# Connectors_CSA.net
KiCad netlist of a schematic drawn in Altium Designer
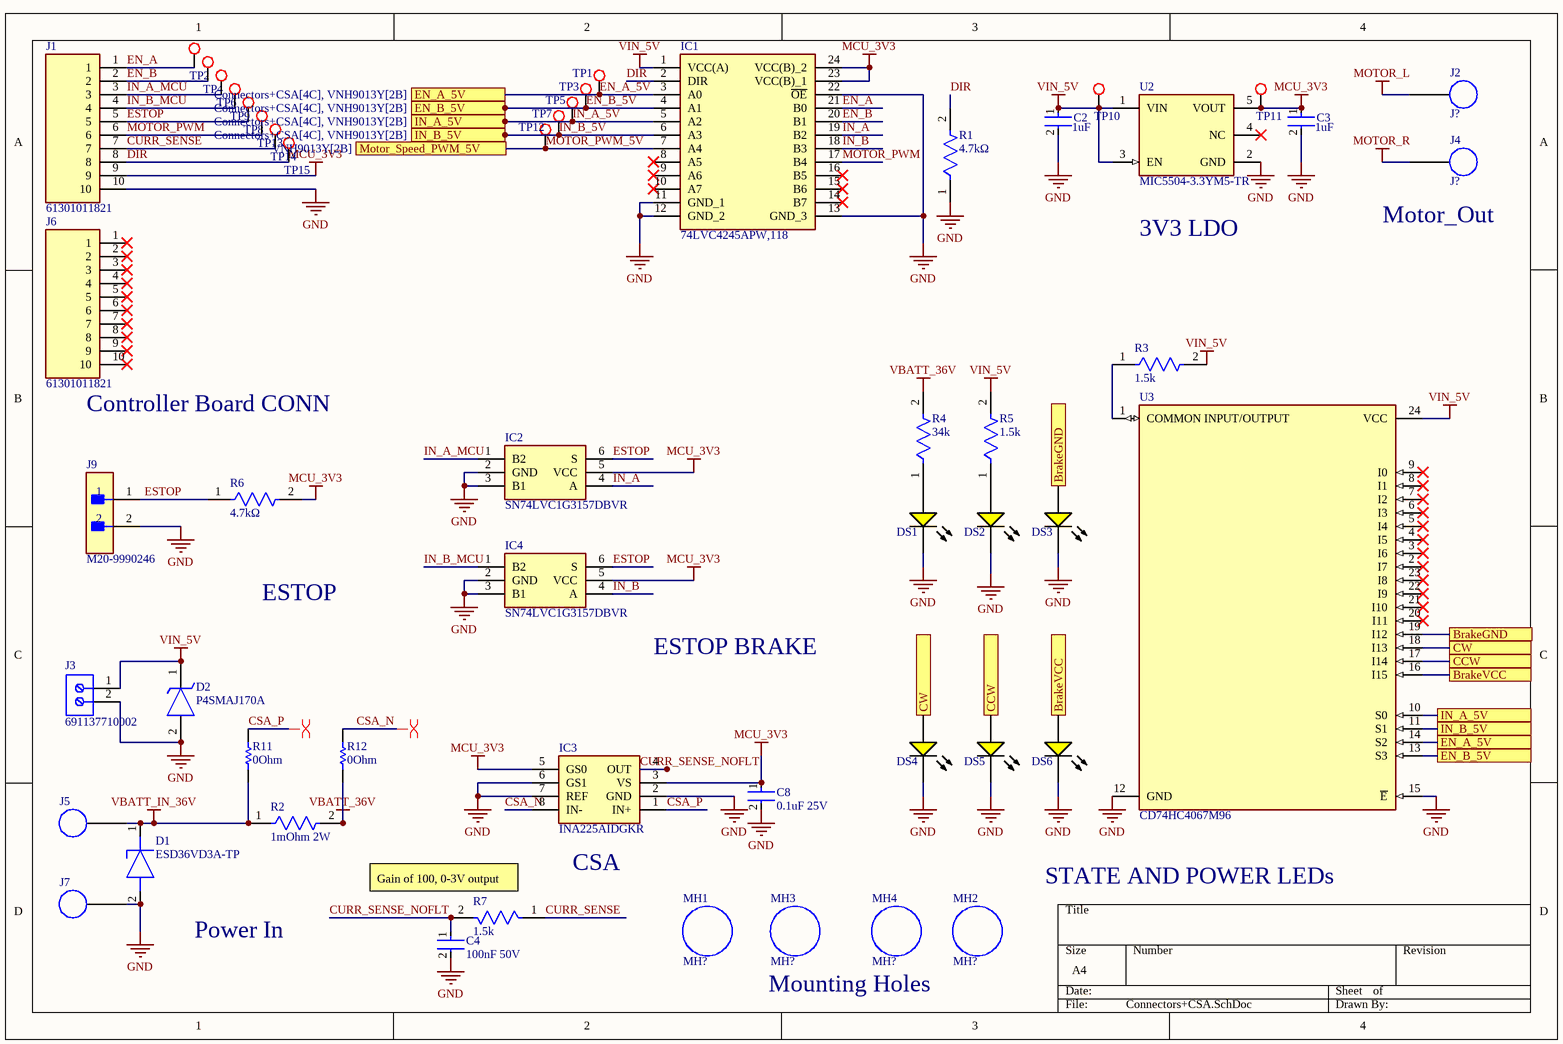
[diagram p0: Connectors+CSA.SchDoc]

(export (version "E")
  (design (tool "Eeschema 10.0.6"))
  (components
    (comp (ref "C2")
      (value "1uF")
      (footprint "FP-CL10-IPC_C")
      (description "Cap Ceramic 1uF 10V X5R ±10% Pad SMD 0603 +85°C T/R")
      (fields (field (name "VOLTAGE") "10V") (field (name "TOLERANCE") "10%"))
      (libsource (lib "Altium Content Vault") (part "b4654b650e69147ec39a6b967a45e02"))
    )
    (comp (ref "C3")
      (value "1uF")
      (footprint "FP-CL10-IPC_C")
      (description "Cap Ceramic 1uF 10V X5R ±10% Pad SMD 0603 +85°C T/R")
      (fields (field (name "VOLTAGE") "10V") (field (name "TOLERANCE") "10%"))
      (libsource (lib "Altium Content Vault") (part "b4654b650e69147ec39a6b967a45e02"))
    )
    (comp (ref "C4")
      (value "100nF 50V")
      (footprint "FP-CL31-IPC_C")
      (description "Cap Ceramic 100nF 50V X7R ±10% SMD 1206 +125°C Embossed T/R")
      (fields (field (name "TOLERANCE") "10%"))
      (libsource (lib "Altium Content Vault") (part "b4654b650e69147ec39a6b967a45e02"))
    )
    (comp (ref "C8")
      (value "0.1uF 25V")
      (footprint "FP-CL21-IPC_C")
      (description "CL21 Series 0805 100nF 25V -20/+80% Tolerance Y5V Multilayer Ceramic Chip Capacitor")
      (fields (field (name "TOLERANCE") "80%"))
      (libsource (lib "Altium Content Vault") (part "b4654b650e69147ec39a6b967a45e02"))
    )
    (comp (ref "D1")
      (value "ESD36VD3A-TP")
      (footprint "SamacSys:SOD2512X115N")
      (description "Diode ESD (Uni-directional)")
      (libsource (lib "*") (part "ESD36VD3A-TP"))
    )
    (comp (ref "D2")
      (value "P4SMAJ170A")
      (footprint "SamacSys:DIOM5027X240N")
      (description "TVS Diode (Uni-directional)")
      (libsource (lib "*") (part "P4SMAJ170A"))
    )
    (comp (ref "DS1")
      (value "HSMY-C190")
      (footprint "AVAG-HSMX-C190_V")
      (description "LED Uni-Color Yellow, 65 mW, 20 mA, -40 to 85 degC, 2-Pin SMD, RoHS, Tape and Reel")
      (fields (field (name "TOLERANCE") "1%"))
      (libsource (lib "Altium Content Vault") (part "LED-YELLOW-AK-2"))
    )
    (comp (ref "DS2")
      (value "HSMY-C190")
      (footprint "AVAG-HSMX-C190_V")
      (description "LED Uni-Color Yellow, 65 mW, 20 mA, -40 to 85 degC, 2-Pin SMD, RoHS, Tape and Reel")
      (fields (field (name "TOLERANCE") "1%"))
      (libsource (lib "Altium Content Vault") (part "LED-YELLOW-AK-2"))
    )
    (comp (ref "DS3")
      (value "HSMY-C190")
      (footprint "AVAG-HSMX-C190_V")
      (description "LED Uni-Color Yellow, 65 mW, 20 mA, -40 to 85 degC, 2-Pin SMD, RoHS, Tape and Reel")
      (fields (field (name "TOLERANCE") "1%"))
      (libsource (lib "Altium Content Vault") (part "LED-YELLOW-AK-2"))
    )
    (comp (ref "DS4")
      (value "HSMY-C190")
      (footprint "AVAG-HSMX-C190_V")
      (description "LED Uni-Color Yellow, 65 mW, 20 mA, -40 to 85 degC, 2-Pin SMD, RoHS, Tape and Reel")
      (fields (field (name "TOLERANCE") "1%"))
      (libsource (lib "Altium Content Vault") (part "LED-YELLOW-AK-2"))
    )
    (comp (ref "DS5")
      (value "HSMY-C190")
      (footprint "AVAG-HSMX-C190_V")
      (description "LED Uni-Color Yellow, 65 mW, 20 mA, -40 to 85 degC, 2-Pin SMD, RoHS, Tape and Reel")
      (fields (field (name "TOLERANCE") "1%"))
      (libsource (lib "Altium Content Vault") (part "LED-YELLOW-AK-2"))
    )
    (comp (ref "DS6")
      (value "HSMY-C190")
      (footprint "AVAG-HSMX-C190_V")
      (description "LED Uni-Color Yellow, 65 mW, 20 mA, -40 to 85 degC, 2-Pin SMD, RoHS, Tape and Reel")
      (fields (field (name "TOLERANCE") "1%"))
      (libsource (lib "Altium Content Vault") (part "LED-YELLOW-AK-2"))
    )
    (comp (ref "IC1")
      (value "74LVC4245APW,118")
      (footprint "SamacSys:SOP65P640X110-24N")
      (description "Integrated Circuit")
      (fields (field (name "MOUSER PART NUMBER") "771-74LVC4245APW-T"))
      (libsource (lib "*") (part "74LVC4245APW,118"))
    )
    (comp (ref "IC2")
      (value "SN74LVC1G3157DBVR")
      (footprint "SamacSys:SOT95P280X145-6N")
      (description "Integrated Circuit")
      (fields (field (name "MOUSER PART NUMBER") "595-SN74LVC1G3157DBV"))
      (libsource (lib "*") (part "SN74LVC1G3157DBVR"))
    )
    (comp (ref "IC3")
      (value "INA225AIDGKR")
      (footprint "SamacSys:SOP65P490X110-8N")
      (description "Integrated Circuit")
      (libsource (lib "*") (part "INA225AIDGKR"))
    )
    (comp (ref "IC4")
      (value "SN74LVC1G3157DBVR")
      (footprint "SamacSys:SOT95P280X145-6N")
      (description "Integrated Circuit")
      (fields (field (name "MOUSER PART NUMBER") "595-SN74LVC1G3157DBV"))
      (libsource (lib "*") (part "SN74LVC1G3157DBVR"))
    )
    (comp (ref "J1")
      (value "61301011821")
      (footprint "SamacSys:RHDR10W60P0X254_1X10_2590X250X850P")
      (description "Connector")
      (fields (field (name "MOUSER PART NUMBER") "710-61301011821"))
      (libsource (lib "*") (part "61301011821"))
    )
    (comp (ref "J2")
      (value "J?")
      (footprint "Power Screw Terminal")
      (libsource (lib "Schlib1") (part "Screw Connector"))
    )
    (comp (ref "J3")
      (value "691137710002")
      (footprint "691137710002")
      (libsource (lib "Altium Content Vault") (part "TBL - 1R - 02P - Screw"))
    )
    (comp (ref "J4")
      (value "J?")
      (footprint "Power Screw Terminal")
      (libsource (lib "Schlib1") (part "Screw Connector"))
    )
    (comp (ref "J5")
      (value "J?")
      (footprint "Power Screw Terminal")
      (libsource (lib "Schlib1") (part "Screw Connector"))
    )
    (comp (ref "J6")
      (value "61301011821")
      (footprint "SamacSys:RHDR10W60P0X254_1X10_2590X250X850P")
      (description "Connector")
      (fields (field (name "MOUSER PART NUMBER") "710-61301011821"))
      (libsource (lib "*") (part "61301011821"))
    )
    (comp (ref "J7")
      (value "J?")
      (footprint "Power Screw Terminal")
      (libsource (lib "Schlib1") (part "Screw Connector"))
    )
    (comp (ref "J9")
      (value "M20-9990246")
      (footprint "FP-M20-9990246-MFG")
      (description "CONN HEADER VERT 2POS 2.54MM")
      (fields
        (field (name "OCTOPART") "https://octopart.com/m20-9990246-harwin-2590635")
        (field (name "MANUFACTURER") "Harwin")
      )
      (libsource (lib "Altium Content Vault") (part "3bc925449376181038e59eaffc5286c"))
    )
    (comp (ref "MH1")
      (value "MH?")
      (footprint "Mounting Hole")
      (libsource (lib "Schlib1") (part "Mounting Hole"))
    )
    (comp (ref "MH2")
      (value "MH?")
      (footprint "Mounting Hole")
      (libsource (lib "Schlib1") (part "Mounting Hole"))
    )
    (comp (ref "MH3")
      (value "MH?")
      (footprint "Mounting Hole")
      (libsource (lib "Schlib1") (part "Mounting Hole"))
    )
    (comp (ref "MH4")
      (value "MH?")
      (footprint "Mounting Hole")
      (libsource (lib "Schlib1") (part "Mounting Hole"))
    )
    (comp (ref "R1")
      (value "4.7kΩ")
      (footprint "FP-RT0805-MFG")
      (description "RES SMD 4.7K OHM 1% 1/8W 0805")
      (fields (field (name "TOLERANCE") "0.0001") (field (name "MANUFACTURER PART NUMBER") "RT0805FRE074K7L"))
      (libsource (lib "Altium Content Vault") (part "1029c3af85768c4190bb7ad29bc67b5"))
    )
    (comp (ref "R2")
      (value "1mOhm 2W")
      (footprint "FP-WSL2512-MFG")
      (fields (field (name "TOLERANCE") "1%"))
      (libsource (lib "Altium Content Vault") (part "1029c3af85768c4190bb7ad29bc67b5"))
    )
    (comp (ref "R3")
      (value "1.5k")
      (footprint "FP-RC1608-IPC_B")
      (description "Res Thick Film 0603 1.5kΩ 1% 0.1W ±100ppm/°C Molded SMD T/R")
      (fields (field (name "TOLERANCE") "1%"))
      (libsource (lib "Altium Content Vault") (part "1029c3af85768c4190bb7ad29bc67b5"))
    )
    (comp (ref "R4")
      (value "34k")
      (footprint "FP-CRCW0805-e3-IPC_B")
      (description "RES Thick Film, 34kΩ, 1%, 0.125W, 100ppm/°C, 0805")
      (fields (field (name "TOLERANCE") "1%"))
      (libsource (lib "Altium Content Vault") (part "1029c3af85768c4190bb7ad29bc67b5"))
    )
    (comp (ref "R5")
      (value "1.5k")
      (footprint "FP-RC1608-IPC_B")
      (description "Res Thick Film 0603 1.5kΩ 1% 0.1W ±100ppm/°C Molded SMD T/R")
      (fields (field (name "TOLERANCE") "1%"))
      (libsource (lib "Altium Content Vault") (part "1029c3af85768c4190bb7ad29bc67b5"))
    )
    (comp (ref "R6")
      (value "4.7kΩ")
      (footprint "FP-RT0805-MFG")
      (description "RES SMD 4.7K OHM 1% 1/8W 0805")
      (fields (field (name "TOLERANCE") "0.0001") (field (name "MANUFACTURER PART NUMBER") "RT0805FRE074K7L"))
      (libsource (lib "Altium Content Vault") (part "1029c3af85768c4190bb7ad29bc67b5"))
    )
    (comp (ref "R7")
      (value "1.5k")
      (footprint "FP-CRCW0603-e3-IPC_A")
      (description "RES Thick Film, 1.5kΩ, 1%, 0.1W, 100ppm/°C, 0603")
      (fields (field (name "TOLERANCE") "1%"))
      (libsource (lib "Altium Content Vault") (part "1029c3af85768c4190bb7ad29bc67b5"))
    )
    (comp (ref "R11")
      (value "0Ohm")
      (footprint "RESC2013X60X35LL10T20")
      (description "Chip Resistor, 0 Ohm, +/- 5%, 125 mW, -55 to 155 degC, 0805 (2012 Metric), RoHS, Tape and Reel")
      (fields (field (name "MANUFACTURER") "Yageo"))
      (libsource (lib "Altium Content Vault") (part "RES-2"))
    )
    (comp (ref "R12")
      (value "0Ohm")
      (footprint "RESC2013X60X35LL10T20")
      (description "Chip Resistor, 0 Ohm, +/- 5%, 125 mW, -55 to 155 degC, 0805 (2012 Metric), RoHS, Tape and Reel")
      (fields (field (name "MANUFACTURER") "Yageo"))
      (libsource (lib "Altium Content Vault") (part "RES-2"))
    )
    (comp (ref "TP1") (value "TP") (footprint "Testpoint") (libsource (lib "Schlib1") (part "Testpoint")))
    (comp (ref "TP2") (value "TP") (footprint "Testpoint") (libsource (lib "Schlib1") (part "Testpoint")))
    (comp (ref "TP3") (value "TP") (footprint "Testpoint") (libsource (lib "Schlib1") (part "Testpoint")))
    (comp (ref "TP4") (value "TP") (footprint "Testpoint") (libsource (lib "Schlib1") (part "Testpoint")))
    (comp (ref "TP5") (value "TP") (footprint "Testpoint") (libsource (lib "Schlib1") (part "Testpoint")))
    (comp (ref "TP6") (value "TP") (footprint "Testpoint") (libsource (lib "Schlib1") (part "Testpoint")))
    (comp (ref "TP7") (value "TP") (footprint "Testpoint") (libsource (lib "Schlib1") (part "Testpoint")))
    (comp (ref "TP8") (value "TP") (footprint "Testpoint") (libsource (lib "Schlib1") (part "Testpoint")))
    (comp (ref "TP9") (value "TP") (footprint "Testpoint") (libsource (lib "Schlib1") (part "Testpoint")))
    (comp (ref "TP10") (value "TP") (footprint "Testpoint") (libsource (lib "Schlib1") (part "Testpoint")))
    (comp (ref "TP11") (value "TP") (footprint "Testpoint") (libsource (lib "Schlib1") (part "Testpoint")))
    (comp (ref "TP12") (value "TP") (footprint "Testpoint") (libsource (lib "Schlib1") (part "Testpoint")))
    (comp (ref "TP13") (value "TP") (footprint "Testpoint") (libsource (lib "Schlib1") (part "Testpoint")))
    (comp (ref "TP14") (value "TP") (footprint "Testpoint") (libsource (lib "Schlib1") (part "Testpoint")))
    (comp (ref "TP15") (value "TP") (footprint "Testpoint") (libsource (lib "Schlib1") (part "Testpoint")))
    (comp (ref "U2")
      (value "MIC5504-3.3YM5-TR")
      (footprint "FP-SOT23-5LD-PL-1-MFG")
      (description "IC REG LINEAR 3.3V 300MA SOT23-5")
      (libsource (lib "Altium Content Vault") (part "96048095611b4a9579e1e315950d302"))
    )
    (comp (ref "U3")
      (value "CD74HC4067M96")
      (footprint "FP-DW0024A-MFG")
      (description "IC MUX/DEMUX 1X16 24SOIC")
      (fields
        (field (name "OCTOPART") "https://octopart.com/cd74hc4067m96-texas+instruments-722802")
        (field (name "MANUFACTURER") "Texas Instruments")
      )
      (libsource (lib "Altium Content Vault") (part "0e3014a41e7f600214dac1b4fa06845"))
    )
  )
  (nets
    (net (code "1") (name "/BrakeGND") (class "Default")
      (node (ref "DS3") (pin "1") (pinfunction "A_1") (pintype "passive"))
      (node (ref "U3") (pin "19") (pinfunction "I12_19") (pintype "input"))
    )
    (net (code "2") (name "/BrakeVCC") (class "Default")
      (node (ref "DS6") (pin "1") (pinfunction "A_1") (pintype "passive"))
      (node (ref "U3") (pin "16") (pinfunction "I15_16") (pintype "input"))
    )
    (net (code "3") (name "/CCW") (class "Default")
      (node (ref "DS5") (pin "1") (pinfunction "A_1") (pintype "passive"))
      (node (ref "U3") (pin "17") (pinfunction "I14_17") (pintype "input"))
    )
    (net (code "4") (name "/CSA_N") (class "Default")
      (node (ref "IC3") (pin "8") (pinfunction "IN-_8") (pintype "passive"))
      (node (ref "R12") (pin "1") (pinfunction "1_1") (pintype "passive"))
    )
    (net (code "5") (name "/CSA_P") (class "Default")
      (node (ref "IC3") (pin "1") (pinfunction "IN+_1") (pintype "passive"))
      (node (ref "R11") (pin "1") (pinfunction "1_1") (pintype "passive"))
    )
    (net (code "6") (name "/CURR_SENSE") (class "Default")
      (node (ref "J1") (pin "7") (pinfunction "7_7") (pintype "passive"))
      (node (ref "R7") (pin "1") (pinfunction "1_1") (pintype "passive"))
      (node (ref "TP14") (pin "0") (pinfunction "0_0") (pintype "passive"))
    )
    (net (code "7") (name "/CURR_SENSE_NOFLT") (class "Default")
      (node (ref "C4") (pin "1") (pinfunction "1_1") (pintype "passive"))
      (node (ref "IC3") (pin "4") (pinfunction "OUT_4") (pintype "passive"))
      (node (ref "R7") (pin "2") (pinfunction "2_2") (pintype "passive"))
    )
    (net (code "8") (name "/CW") (class "Default")
      (node (ref "DS4") (pin "1") (pinfunction "A_1") (pintype "passive"))
      (node (ref "U3") (pin "18") (pinfunction "I13_18") (pintype "input"))
    )
    (net (code "9") (name "/DIR") (class "Default")
      (node (ref "IC1") (pin "2") (pinfunction "DIR_2") (pintype "passive"))
      (node (ref "J1") (pin "8") (pinfunction "8_8") (pintype "passive"))
      (node (ref "R1") (pin "2") (pinfunction "2_2") (pintype "passive"))
      (node (ref "TP15") (pin "0") (pinfunction "0_0") (pintype "passive"))
    )
    (net (code "10") (name "/EN_A") (class "Default")
      (node (ref "IC1") (pin "21") (pinfunction "B0_21") (pintype "passive"))
      (node (ref "J1") (pin "1") (pinfunction "1_1") (pintype "passive"))
      (node (ref "TP2") (pin "0") (pinfunction "0_0") (pintype "passive"))
    )
    (net (code "11") (name "/EN_A_5V") (class "Default")
      (node (ref "IC1") (pin "3") (pinfunction "A0_3") (pintype "passive"))
      (node (ref "TP1") (pin "0") (pinfunction "0_0") (pintype "passive"))
      (node (ref "U3") (pin "14") (pinfunction "S2_14") (pintype "input"))
    )
    (net (code "12") (name "/EN_B") (class "Default")
      (node (ref "IC1") (pin "20") (pinfunction "B1_20") (pintype "passive"))
      (node (ref "J1") (pin "2") (pinfunction "2_2") (pintype "passive"))
      (node (ref "TP4") (pin "0") (pinfunction "0_0") (pintype "passive"))
    )
    (net (code "13") (name "/EN_B_5V") (class "Default")
      (node (ref "IC1") (pin "4") (pinfunction "A1_4") (pintype "passive"))
      (node (ref "TP3") (pin "0") (pinfunction "0_0") (pintype "passive"))
      (node (ref "U3") (pin "13") (pinfunction "S3_13") (pintype "input"))
    )
    (net (code "14") (name "/ESTOP") (class "Default")
      (node (ref "IC2") (pin "6") (pinfunction "S_6") (pintype "passive"))
      (node (ref "IC4") (pin "6") (pinfunction "S_6") (pintype "passive"))
      (node (ref "J1") (pin "5") (pinfunction "5_5") (pintype "passive"))
      (node (ref "J9") (pin "1") (pinfunction "1_1") (pintype "passive"))
      (node (ref "R6") (pin "1") (pinfunction "1_1") (pintype "passive"))
      (node (ref "TP8") (pin "0") (pinfunction "0_0") (pintype "passive"))
    )
    (net (code "15") (name "/IN_A") (class "Default")
      (node (ref "IC1") (pin "19") (pinfunction "B2_19") (pintype "passive"))
      (node (ref "IC2") (pin "4") (pinfunction "A_4") (pintype "passive"))
    )
    (net (code "16") (name "/IN_A_5V") (class "Default")
      (node (ref "IC1") (pin "5") (pinfunction "A2_5") (pintype "passive"))
      (node (ref "TP5") (pin "0") (pinfunction "0_0") (pintype "passive"))
      (node (ref "U3") (pin "10") (pinfunction "S0_10") (pintype "input"))
    )
    (net (code "17") (name "/IN_A_MCU") (class "Default")
      (node (ref "IC2") (pin "1") (pinfunction "B2_1") (pintype "passive"))
      (node (ref "J1") (pin "3") (pinfunction "3_3") (pintype "passive"))
      (node (ref "TP6") (pin "0") (pinfunction "0_0") (pintype "passive"))
    )
    (net (code "18") (name "/IN_B") (class "Default")
      (node (ref "IC1") (pin "18") (pinfunction "B3_18") (pintype "passive"))
      (node (ref "IC4") (pin "4") (pinfunction "A_4") (pintype "passive"))
    )
    (net (code "19") (name "/IN_B_5V") (class "Default")
      (node (ref "IC1") (pin "6") (pinfunction "A3_6") (pintype "passive"))
      (node (ref "TP7") (pin "0") (pinfunction "0_0") (pintype "passive"))
      (node (ref "U3") (pin "11") (pinfunction "S1_11") (pintype "input"))
    )
    (net (code "20") (name "/IN_B_MCU") (class "Default")
      (node (ref "IC4") (pin "1") (pinfunction "B2_1") (pintype "passive"))
      (node (ref "J1") (pin "4") (pinfunction "4_4") (pintype "passive"))
      (node (ref "TP9") (pin "0") (pinfunction "0_0") (pintype "passive"))
    )
    (net (code "21") (name "/MOTOR_PWM") (class "Default")
      (node (ref "IC1") (pin "17") (pinfunction "B4_17") (pintype "passive"))
      (node (ref "J1") (pin "6") (pinfunction "6_6") (pintype "passive"))
      (node (ref "TP13") (pin "0") (pinfunction "0_0") (pintype "passive"))
    )
    (net (code "22") (name "/MOTOR_PWM_5V") (class "Default")
      (node (ref "IC1") (pin "7") (pinfunction "A4_7") (pintype "passive"))
      (node (ref "TP12") (pin "0") (pinfunction "0_0") (pintype "passive"))
    )
    (net (code "23") (name "GND") (class "Default")
      (node (ref "C2") (pin "2") (pinfunction "2_2") (pintype "passive"))
      (node (ref "C3") (pin "2") (pinfunction "2_2") (pintype "passive"))
      (node (ref "C4") (pin "2") (pinfunction "2_2") (pintype "passive"))
      (node (ref "C8") (pin "2") (pinfunction "2_2") (pintype "passive"))
      (node (ref "D1") (pin "2") (pinfunction "A_2") (pintype "passive"))
      (node (ref "D2") (pin "2") (pinfunction "A_2") (pintype "passive"))
      (node (ref "DS1") (pin "2") (pinfunction "K_2") (pintype "passive"))
      (node (ref "DS2") (pin "2") (pinfunction "K_2") (pintype "passive"))
      (node (ref "DS3") (pin "2") (pinfunction "K_2") (pintype "passive"))
      (node (ref "DS4") (pin "2") (pinfunction "K_2") (pintype "passive"))
      (node (ref "DS5") (pin "2") (pinfunction "K_2") (pintype "passive"))
      (node (ref "DS6") (pin "2") (pinfunction "K_2") (pintype "passive"))
      (node (ref "IC1") (pin "11") (pinfunction "GND_1_11") (pintype "passive"))
      (node (ref "IC1") (pin "12") (pinfunction "GND_2_12") (pintype "passive"))
      (node (ref "IC1") (pin "13") (pinfunction "GND_3_13") (pintype "passive"))
      (node (ref "IC1") (pin "22") (pinfunction "~{OE}_22") (pintype "passive"))
      (node (ref "IC2") (pin "2") (pinfunction "GND_2") (pintype "passive"))
      (node (ref "IC2") (pin "3") (pinfunction "B1_3") (pintype "passive"))
      (node (ref "IC3") (pin "2") (pinfunction "GND_2") (pintype "passive"))
      (node (ref "IC3") (pin "6") (pinfunction "GS1_6") (pintype "passive"))
      (node (ref "IC3") (pin "7") (pinfunction "REF_7") (pintype "passive"))
      (node (ref "IC4") (pin "2") (pinfunction "GND_2") (pintype "passive"))
      (node (ref "IC4") (pin "3") (pinfunction "B1_3") (pintype "passive"))
      (node (ref "J1") (pin "10") (pinfunction "10_10") (pintype "passive"))
      (node (ref "J3") (pin "2") (pinfunction "2_2") (pintype "passive"))
      (node (ref "J7") (pin "1") (pinfunction "1_1") (pintype "passive"))
      (node (ref "J9") (pin "2") (pinfunction "2_2") (pintype "passive"))
      (node (ref "R1") (pin "1") (pinfunction "1_1") (pintype "passive"))
      (node (ref "U2") (pin "2") (pinfunction "GND_2") (pintype "power_in"))
      (node (ref "U3") (pin "12") (pinfunction "GND_12") (pintype "power_in"))
      (node (ref "U3") (pin "15") (pinfunction "~{E}_15") (pintype "input"))
    )
    (net (code "24") (name "MCU_3V3") (class "Default")
      (node (ref "C3") (pin "1") (pinfunction "1_1") (pintype "passive"))
      (node (ref "C8") (pin "1") (pinfunction "1_1") (pintype "passive"))
      (node (ref "IC1") (pin "23") (pinfunction "VCC(B)_1_23") (pintype "passive"))
      (node (ref "IC1") (pin "24") (pinfunction "VCC(B)_2_24") (pintype "passive"))
      (node (ref "IC2") (pin "5") (pinfunction "VCC_5") (pintype "passive"))
      (node (ref "IC3") (pin "3") (pinfunction "VS_3") (pintype "passive"))
      (node (ref "IC3") (pin "5") (pinfunction "GS0_5") (pintype "passive"))
      (node (ref "IC4") (pin "5") (pinfunction "VCC_5") (pintype "passive"))
      (node (ref "J1") (pin "9") (pinfunction "9_9") (pintype "passive"))
      (node (ref "R6") (pin "2") (pinfunction "2_2") (pintype "passive"))
      (node (ref "TP11") (pin "0") (pinfunction "0_0") (pintype "passive"))
      (node (ref "U2") (pin "5") (pinfunction "VOUT_5") (pintype "power_in"))
    )
    (net (code "25") (name "MOTOR_L") (class "Default")
      (node (ref "J2") (pin "1") (pinfunction "1_1") (pintype "passive"))
    )
    (net (code "26") (name "MOTOR_R") (class "Default")
      (node (ref "J4") (pin "1") (pinfunction "1_1") (pintype "passive"))
    )
    (net (code "27") (name "Net-(DS1-A)") (class "Default")
      (node (ref "DS1") (pin "1") (pinfunction "A_1") (pintype "passive"))
      (node (ref "R4") (pin "1") (pinfunction "1_1") (pintype "passive"))
    )
    (net (code "28") (name "Net-(DS2-A)") (class "Default")
      (node (ref "DS2") (pin "1") (pinfunction "A_1") (pintype "passive"))
      (node (ref "R5") (pin "1") (pinfunction "1_1") (pintype "passive"))
    )
    (net (code "29") (name "Net-(U3-COMMON_INPUT{slash}OUTPUT)") (class "Default")
      (node (ref "R3") (pin "1") (pinfunction "1_1") (pintype "passive"))
      (node (ref "U3") (pin "1") (pinfunction "COMMON_INPUT/OUTPUT_1") (pintype "bidirectional"))
    )
    (net (code "30") (name "VBATT_36V") (class "Default")
      (node (ref "R12") (pin "2") (pinfunction "2_2") (pintype "passive"))
      (node (ref "R2") (pin "2") (pinfunction "2_2") (pintype "passive"))
      (node (ref "R4") (pin "2") (pinfunction "2_2") (pintype "passive"))
    )
    (net (code "31") (name "VBATT_IN_36V") (class "Default")
      (node (ref "D1") (pin "1") (pinfunction "K_1") (pintype "passive"))
      (node (ref "J5") (pin "1") (pinfunction "1_1") (pintype "passive"))
      (node (ref "R11") (pin "2") (pinfunction "2_2") (pintype "passive"))
      (node (ref "R2") (pin "1") (pinfunction "1_1") (pintype "passive"))
    )
    (net (code "32") (name "VIN_5V") (class "Default")
      (node (ref "C2") (pin "1") (pinfunction "1_1") (pintype "passive"))
      (node (ref "D2") (pin "1") (pinfunction "K_1") (pintype "passive"))
      (node (ref "IC1") (pin "1") (pinfunction "VCC(A)_1") (pintype "passive"))
      (node (ref "J3") (pin "1") (pinfunction "1_1") (pintype "passive"))
      (node (ref "R3") (pin "2") (pinfunction "2_2") (pintype "passive"))
      (node (ref "R5") (pin "2") (pinfunction "2_2") (pintype "passive"))
      (node (ref "TP10") (pin "0") (pinfunction "0_0") (pintype "passive"))
      (node (ref "U2") (pin "1") (pinfunction "VIN_1") (pintype "power_in"))
      (node (ref "U2") (pin "3") (pinfunction "EN_3") (pintype "input"))
      (node (ref "U3") (pin "24") (pinfunction "VCC_24") (pintype "power_in"))
    )
    (net (code "33") (name "unconnected-(IC1-A5-Pad8)") (class "Default")
      (node (ref "IC1") (pin "8") (pinfunction "A5_8") (pintype "passive+no_connect"))
    )
    (net (code "34") (name "unconnected-(IC1-A6-Pad9)") (class "Default")
      (node (ref "IC1") (pin "9") (pinfunction "A6_9") (pintype "passive+no_connect"))
    )
    (net (code "35") (name "unconnected-(IC1-A7-Pad10)") (class "Default")
      (node (ref "IC1") (pin "10") (pinfunction "A7_10") (pintype "passive+no_connect"))
    )
    (net (code "36") (name "unconnected-(IC1-B5-Pad16)") (class "Default")
      (node (ref "IC1") (pin "16") (pinfunction "B5_16") (pintype "passive+no_connect"))
    )
    (net (code "37") (name "unconnected-(IC1-B6-Pad15)") (class "Default")
      (node (ref "IC1") (pin "15") (pinfunction "B6_15") (pintype "passive+no_connect"))
    )
    (net (code "38") (name "unconnected-(IC1-B7-Pad14)") (class "Default")
      (node (ref "IC1") (pin "14") (pinfunction "B7_14") (pintype "passive+no_connect"))
    )
    (net (code "39") (name "unconnected-(J6-Pad1)") (class "Default")
      (node (ref "J6") (pin "1") (pinfunction "1_1") (pintype "passive+no_connect"))
    )
    (net (code "40") (name "unconnected-(J6-Pad2)") (class "Default")
      (node (ref "J6") (pin "2") (pinfunction "2_2") (pintype "passive+no_connect"))
    )
    (net (code "41") (name "unconnected-(J6-Pad3)") (class "Default")
      (node (ref "J6") (pin "3") (pinfunction "3_3") (pintype "passive+no_connect"))
    )
    (net (code "42") (name "unconnected-(J6-Pad4)") (class "Default")
      (node (ref "J6") (pin "4") (pinfunction "4_4") (pintype "passive+no_connect"))
    )
    (net (code "43") (name "unconnected-(J6-Pad5)") (class "Default")
      (node (ref "J6") (pin "5") (pinfunction "5_5") (pintype "passive+no_connect"))
    )
    (net (code "44") (name "unconnected-(J6-Pad6)") (class "Default")
      (node (ref "J6") (pin "6") (pinfunction "6_6") (pintype "passive+no_connect"))
    )
    (net (code "45") (name "unconnected-(J6-Pad7)") (class "Default")
      (node (ref "J6") (pin "7") (pinfunction "7_7") (pintype "passive+no_connect"))
    )
    (net (code "46") (name "unconnected-(J6-Pad8)") (class "Default")
      (node (ref "J6") (pin "8") (pinfunction "8_8") (pintype "passive+no_connect"))
    )
    (net (code "47") (name "unconnected-(J6-Pad9)") (class "Default")
      (node (ref "J6") (pin "9") (pinfunction "9_9") (pintype "passive+no_connect"))
    )
    (net (code "48") (name "unconnected-(J6-Pad10)") (class "Default")
      (node (ref "J6") (pin "10") (pinfunction "10_10") (pintype "passive+no_connect"))
    )
    (net (code "49") (name "unconnected-(U2-NC-Pad4)") (class "Default")
      (node (ref "U2") (pin "4") (pinfunction "NC_4") (pintype "passive+no_connect"))
    )
    (net (code "50") (name "unconnected-(U3-I0-Pad9)") (class "Default")
      (node (ref "U3") (pin "9") (pinfunction "I0_9") (pintype "input+no_connect"))
    )
    (net (code "51") (name "unconnected-(U3-I1-Pad8)") (class "Default")
      (node (ref "U3") (pin "8") (pinfunction "I1_8") (pintype "input+no_connect"))
    )
    (net (code "52") (name "unconnected-(U3-I2-Pad7)") (class "Default")
      (node (ref "U3") (pin "7") (pinfunction "I2_7") (pintype "input+no_connect"))
    )
    (net (code "53") (name "unconnected-(U3-I3-Pad6)") (class "Default")
      (node (ref "U3") (pin "6") (pinfunction "I3_6") (pintype "input+no_connect"))
    )
    (net (code "54") (name "unconnected-(U3-I4-Pad5)") (class "Default")
      (node (ref "U3") (pin "5") (pinfunction "I4_5") (pintype "input+no_connect"))
    )
    (net (code "55") (name "unconnected-(U3-I5-Pad4)") (class "Default")
      (node (ref "U3") (pin "4") (pinfunction "I5_4") (pintype "input+no_connect"))
    )
    (net (code "56") (name "unconnected-(U3-I6-Pad3)") (class "Default")
      (node (ref "U3") (pin "3") (pinfunction "I6_3") (pintype "input+no_connect"))
    )
    (net (code "57") (name "unconnected-(U3-I7-Pad2)") (class "Default")
      (node (ref "U3") (pin "2") (pinfunction "I7_2") (pintype "input+no_connect"))
    )
    (net (code "58") (name "unconnected-(U3-I8-Pad23)") (class "Default")
      (node (ref "U3") (pin "23") (pinfunction "I8_23") (pintype "input+no_connect"))
    )
    (net (code "59") (name "unconnected-(U3-I9-Pad22)") (class "Default")
      (node (ref "U3") (pin "22") (pinfunction "I9_22") (pintype "input+no_connect"))
    )
    (net (code "60") (name "unconnected-(U3-I10-Pad21)") (class "Default")
      (node (ref "U3") (pin "21") (pinfunction "I10_21") (pintype "input+no_connect"))
    )
    (net (code "61") (name "unconnected-(U3-I11-Pad20)") (class "Default")
      (node (ref "U3") (pin "20") (pinfunction "I11_20") (pintype "input+no_connect"))
    )
  )
)
